# schematic.net
KiCad netlist of a schematic drawn in EAGLE
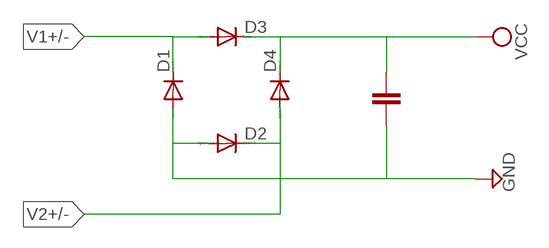
[diagram p0: schematic, sheet 1]

(export (version "E")
  (design (tool "Eeschema 10.0.6"))
  (components
    (comp (ref "D1")
      (value "1N4004")
      (footprint "eagle-import:DO41-10")
      (libsource (lib "eagle-import") (part "1N4004"))
    )
    (comp (ref "D2")
      (value "1N4004")
      (footprint "eagle-import:DO41-10")
      (libsource (lib "eagle-import") (part "1N4004"))
    )
    (comp (ref "D3")
      (value "1N4004")
      (footprint "eagle-import:DO41-10")
      (libsource (lib "eagle-import") (part "1N4004"))
    )
    (comp (ref "D4")
      (value "1N4004")
      (footprint "eagle-import:DO41-10")
      (libsource (lib "eagle-import") (part "1N4004"))
    )
  )
  (nets
    (net (code "1") (name "GND") (class "Default")
      (node (ref "D1") (pin "A") (pinfunction "A_A") (pintype "passive"))
      (node (ref "D2") (pin "A") (pinfunction "A_A") (pintype "passive"))
    )
    (net (code "2") (name "V1+{slash}-") (class "Default")
      (node (ref "D1") (pin "C") (pinfunction "C_C") (pintype "passive"))
      (node (ref "D3") (pin "A") (pinfunction "A_A") (pintype "passive"))
    )
    (net (code "3") (name "V2+{slash}-") (class "Default")
      (node (ref "D2") (pin "C") (pinfunction "C_C") (pintype "passive"))
      (node (ref "D4") (pin "A") (pinfunction "A_A") (pintype "passive"))
    )
    (net (code "4") (name "VCC") (class "Default")
      (node (ref "D3") (pin "C") (pinfunction "C_C") (pintype "passive"))
      (node (ref "D4") (pin "C") (pinfunction "C_C") (pintype "passive"))
    )
  )
)
